# 8_ch_CV_buffer_design_block.net
KiCad netlist of a schematic drawn in EAGLE
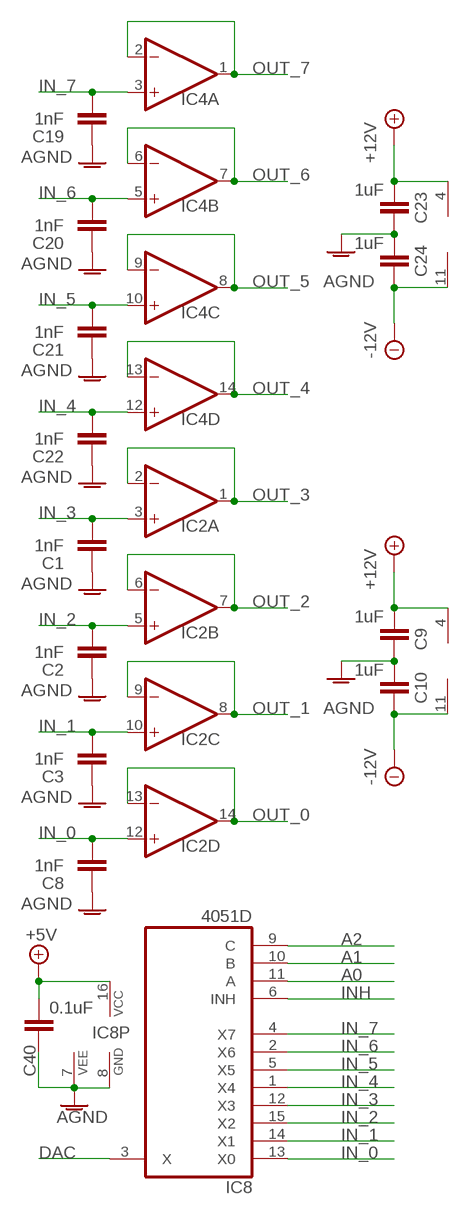
[diagram p0: schematic, sheet 1]

(export (version "E")
  (design (tool "Eeschema 10.0.6"))
  (components
    (comp (ref "C1")
      (value "1nF")
      (footprint "eagle-import:C0603-J")
      (libsource (lib "eagle-import") (part "C-EU-J0603"))
    )
    (comp (ref "C2")
      (value "1nF")
      (footprint "eagle-import:C0603-J")
      (libsource (lib "eagle-import") (part "C-EU-J0603"))
    )
    (comp (ref "C3")
      (value "1nF")
      (footprint "eagle-import:C0603-J")
      (libsource (lib "eagle-import") (part "C-EU-J0603"))
    )
    (comp (ref "C8")
      (value "1nF")
      (footprint "eagle-import:C0603-J")
      (libsource (lib "eagle-import") (part "C-EU-J0603"))
    )
    (comp (ref "C9")
      (value "1uF")
      (footprint "eagle-import:C0402-J")
      (libsource (lib "eagle-import") (part "C-EU-J0402"))
    )
    (comp (ref "C10")
      (value "1uF")
      (footprint "eagle-import:C0402-J")
      (libsource (lib "eagle-import") (part "C-EU-J0402"))
    )
    (comp (ref "C19")
      (value "1nF")
      (footprint "eagle-import:C0603-J")
      (libsource (lib "eagle-import") (part "C-EU-J0603"))
    )
    (comp (ref "C20")
      (value "1nF")
      (footprint "eagle-import:C0603-J")
      (libsource (lib "eagle-import") (part "C-EU-J0603"))
    )
    (comp (ref "C21")
      (value "1nF")
      (footprint "eagle-import:C0603-J")
      (libsource (lib "eagle-import") (part "C-EU-J0603"))
    )
    (comp (ref "C22")
      (value "1nF")
      (footprint "eagle-import:C0603-J")
      (libsource (lib "eagle-import") (part "C-EU-J0603"))
    )
    (comp (ref "C23")
      (value "1uF")
      (footprint "eagle-import:C0402-J")
      (libsource (lib "eagle-import") (part "C-EU-J0402"))
    )
    (comp (ref "C24")
      (value "1uF")
      (footprint "eagle-import:C0402-J")
      (libsource (lib "eagle-import") (part "C-EU-J0402"))
    )
    (comp (ref "C40")
      (value "0.1uF")
      (footprint "eagle-import:C0402-J")
      (libsource (lib "eagle-import") (part "C-EU-J0402"))
    )
    (comp (ref "IC2")
      (value "TL074JT")
      (footprint "eagle-import:TSSOP14J")
      (libsource (lib "eagle-import") (part "TL074JT"))
    )
    (comp (ref "IC4")
      (value "TL074JT")
      (footprint "eagle-import:TSSOP14J")
      (libsource (lib "eagle-import") (part "TL074JT"))
    )
    (comp (ref "IC8")
      (value "4051D")
      (footprint "eagle-import:SO16")
      (libsource (lib "eagle-import") (part "4051D"))
    )
  )
  (nets
    (net (code "1") (name "+5V") (class "Default")
      (node (ref "C40") (pin "2") (pinfunction "2_2") (pintype "passive"))
      (node (ref "IC8") (pin "16") (pinfunction "VCC_16") (pintype "power_in"))
    )
    (net (code "2") (name "+12V") (class "Default")
      (node (ref "C23") (pin "1") (pinfunction "1_1") (pintype "passive"))
      (node (ref "C9") (pin "1") (pinfunction "1_1") (pintype "passive"))
      (node (ref "IC2") (pin "4") (pinfunction "V+_4") (pintype "power_in"))
      (node (ref "IC4") (pin "4") (pinfunction "V+_4") (pintype "power_in"))
    )
    (net (code "3") (name "-12V") (class "Default")
      (node (ref "C10") (pin "2") (pinfunction "2_2") (pintype "passive"))
      (node (ref "C24") (pin "2") (pinfunction "2_2") (pintype "passive"))
      (node (ref "IC2") (pin "11") (pinfunction "V-_11") (pintype "power_in"))
      (node (ref "IC4") (pin "11") (pinfunction "V-_11") (pintype "power_in"))
    )
    (net (code "4") (name "/A0") (class "Default")
      (node (ref "IC8") (pin "11") (pinfunction "A_11") (pintype "input"))
    )
    (net (code "5") (name "/A1") (class "Default")
      (node (ref "IC8") (pin "10") (pinfunction "B_10") (pintype "input"))
    )
    (net (code "6") (name "/A2") (class "Default")
      (node (ref "IC8") (pin "9") (pinfunction "C_9") (pintype "input"))
    )
    (net (code "7") (name "/DAC") (class "Default")
      (node (ref "IC8") (pin "3") (pinfunction "X_3") (pintype "bidirectional"))
    )
    (net (code "8") (name "/INH") (class "Default")
      (node (ref "IC8") (pin "6") (pinfunction "INH_6") (pintype "input"))
    )
    (net (code "9") (name "/IN_0") (class "Default")
      (node (ref "C8") (pin "2") (pinfunction "2_2") (pintype "passive"))
      (node (ref "IC2") (pin "12") (pinfunction "+IN_12") (pintype "input"))
      (node (ref "IC8") (pin "13") (pinfunction "X0_13") (pintype "bidirectional"))
    )
    (net (code "10") (name "/IN_1") (class "Default")
      (node (ref "C3") (pin "2") (pinfunction "2_2") (pintype "passive"))
      (node (ref "IC2") (pin "10") (pinfunction "+IN_10") (pintype "input"))
      (node (ref "IC8") (pin "14") (pinfunction "X1_14") (pintype "bidirectional"))
    )
    (net (code "11") (name "/IN_2") (class "Default")
      (node (ref "C2") (pin "2") (pinfunction "2_2") (pintype "passive"))
      (node (ref "IC2") (pin "5") (pinfunction "+IN_5") (pintype "input"))
      (node (ref "IC8") (pin "15") (pinfunction "X2_15") (pintype "bidirectional"))
    )
    (net (code "12") (name "/IN_3") (class "Default")
      (node (ref "C1") (pin "2") (pinfunction "2_2") (pintype "passive"))
      (node (ref "IC2") (pin "3") (pinfunction "+IN_3") (pintype "input"))
      (node (ref "IC8") (pin "12") (pinfunction "X3_12") (pintype "bidirectional"))
    )
    (net (code "13") (name "/IN_4") (class "Default")
      (node (ref "C22") (pin "2") (pinfunction "2_2") (pintype "passive"))
      (node (ref "IC4") (pin "12") (pinfunction "+IN_12") (pintype "input"))
      (node (ref "IC8") (pin "1") (pinfunction "X4_1") (pintype "bidirectional"))
    )
    (net (code "14") (name "/IN_5") (class "Default")
      (node (ref "C21") (pin "2") (pinfunction "2_2") (pintype "passive"))
      (node (ref "IC4") (pin "10") (pinfunction "+IN_10") (pintype "input"))
      (node (ref "IC8") (pin "5") (pinfunction "X5_5") (pintype "bidirectional"))
    )
    (net (code "15") (name "/IN_6") (class "Default")
      (node (ref "C20") (pin "2") (pinfunction "2_2") (pintype "passive"))
      (node (ref "IC4") (pin "5") (pinfunction "+IN_5") (pintype "input"))
      (node (ref "IC8") (pin "2") (pinfunction "X6_2") (pintype "bidirectional"))
    )
    (net (code "16") (name "/IN_7") (class "Default")
      (node (ref "C19") (pin "2") (pinfunction "2_2") (pintype "passive"))
      (node (ref "IC4") (pin "3") (pinfunction "+IN_3") (pintype "input"))
      (node (ref "IC8") (pin "4") (pinfunction "X7_4") (pintype "bidirectional"))
    )
    (net (code "17") (name "/OUT_0") (class "Default")
      (node (ref "IC2") (pin "13") (pinfunction "-IN_13") (pintype "input"))
      (node (ref "IC2") (pin "14") (pinfunction "OUT_14") (pintype "output"))
    )
    (net (code "18") (name "/OUT_1") (class "Default")
      (node (ref "IC2") (pin "8") (pinfunction "OUT_8") (pintype "output"))
      (node (ref "IC2") (pin "9") (pinfunction "-IN_9") (pintype "input"))
    )
    (net (code "19") (name "/OUT_2") (class "Default")
      (node (ref "IC2") (pin "6") (pinfunction "-IN_6") (pintype "input"))
      (node (ref "IC2") (pin "7") (pinfunction "OUT_7") (pintype "output"))
    )
    (net (code "20") (name "/OUT_3") (class "Default")
      (node (ref "IC2") (pin "1") (pinfunction "OUT_1") (pintype "output"))
      (node (ref "IC2") (pin "2") (pinfunction "-IN_2") (pintype "input"))
    )
    (net (code "21") (name "/OUT_4") (class "Default")
      (node (ref "IC4") (pin "13") (pinfunction "-IN_13") (pintype "input"))
      (node (ref "IC4") (pin "14") (pinfunction "OUT_14") (pintype "output"))
    )
    (net (code "22") (name "/OUT_5") (class "Default")
      (node (ref "IC4") (pin "8") (pinfunction "OUT_8") (pintype "output"))
      (node (ref "IC4") (pin "9") (pinfunction "-IN_9") (pintype "input"))
    )
    (net (code "23") (name "/OUT_6") (class "Default")
      (node (ref "IC4") (pin "6") (pinfunction "-IN_6") (pintype "input"))
      (node (ref "IC4") (pin "7") (pinfunction "OUT_7") (pintype "output"))
    )
    (net (code "24") (name "/OUT_7") (class "Default")
      (node (ref "IC4") (pin "1") (pinfunction "OUT_1") (pintype "output"))
      (node (ref "IC4") (pin "2") (pinfunction "-IN_2") (pintype "input"))
    )
    (net (code "25") (name "AGND") (class "Default")
      (node (ref "C1") (pin "1") (pinfunction "1_1") (pintype "passive"))
      (node (ref "C10") (pin "1") (pinfunction "1_1") (pintype "passive"))
      (node (ref "C19") (pin "1") (pinfunction "1_1") (pintype "passive"))
      (node (ref "C2") (pin "1") (pinfunction "1_1") (pintype "passive"))
      (node (ref "C20") (pin "1") (pinfunction "1_1") (pintype "passive"))
      (node (ref "C21") (pin "1") (pinfunction "1_1") (pintype "passive"))
      (node (ref "C22") (pin "1") (pinfunction "1_1") (pintype "passive"))
      (node (ref "C23") (pin "2") (pinfunction "2_2") (pintype "passive"))
      (node (ref "C24") (pin "1") (pinfunction "1_1") (pintype "passive"))
      (node (ref "C3") (pin "1") (pinfunction "1_1") (pintype "passive"))
      (node (ref "C40") (pin "1") (pinfunction "1_1") (pintype "passive"))
      (node (ref "C8") (pin "1") (pinfunction "1_1") (pintype "passive"))
      (node (ref "C9") (pin "2") (pinfunction "2_2") (pintype "passive"))
      (node (ref "IC8") (pin "7") (pinfunction "VEE_7") (pintype "power_in"))
      (node (ref "IC8") (pin "8") (pinfunction "GND_8") (pintype "power_in"))
    )
  )
)
